# EEGAmp_SMT_MountHole_Castellated.net
KiCad netlist of a schematic drawn in EAGLE
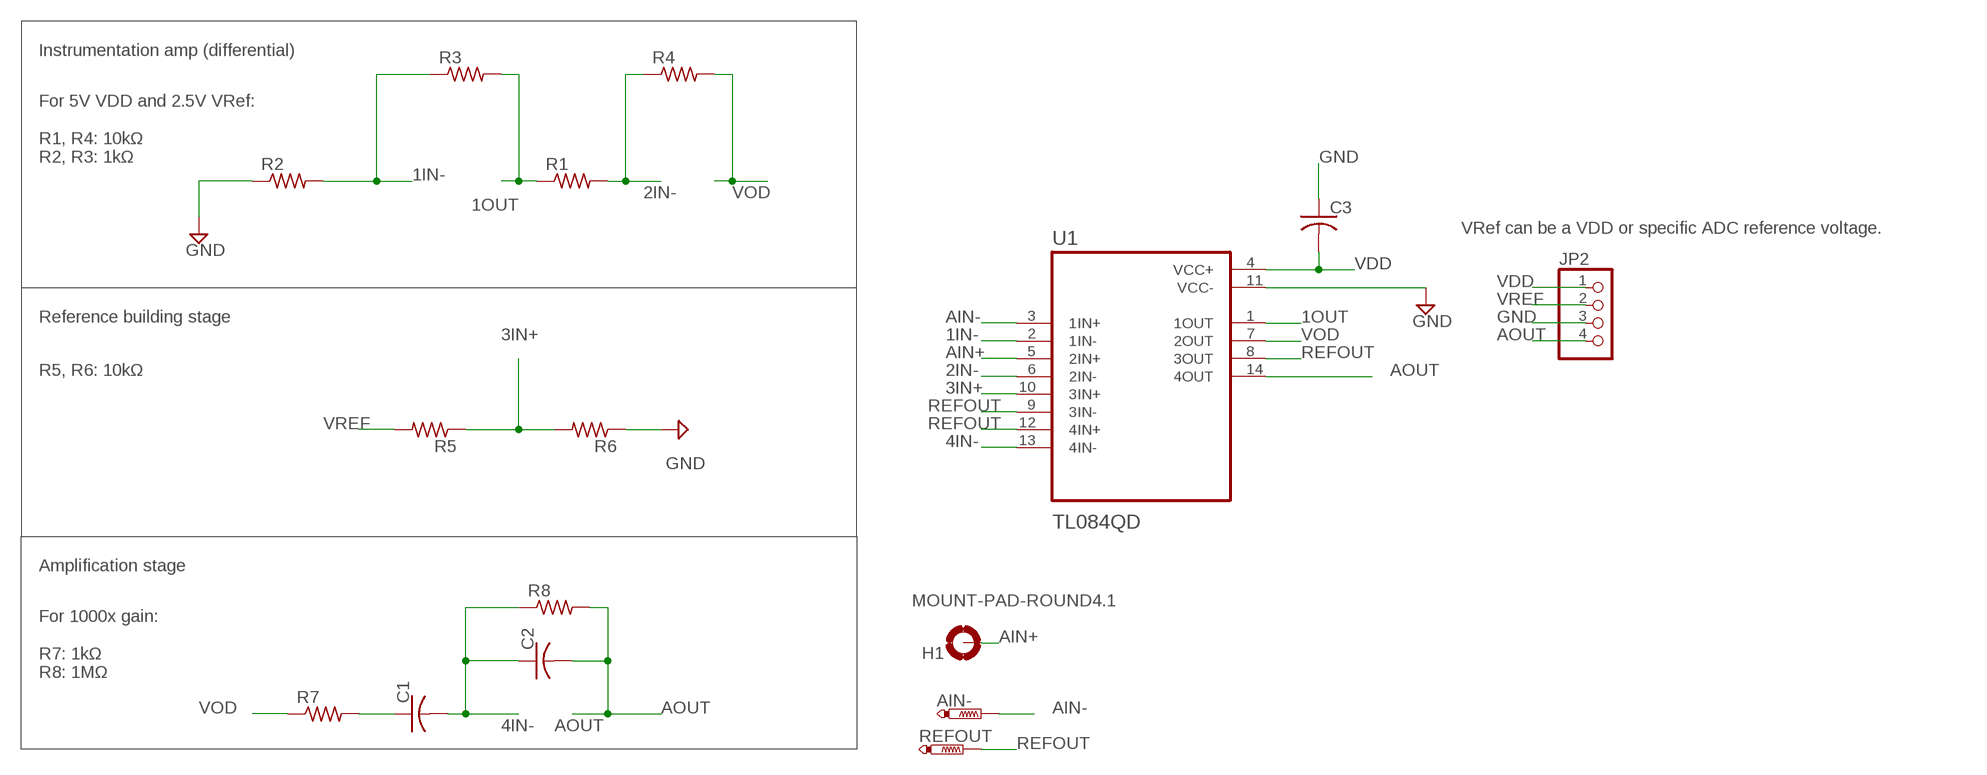
[diagram p0: schematic, sheet 1]

(export (version "E")
  (design (tool "Eeschema 10.0.6"))
  (components
    (comp (ref "AIN-")
      (value "PTR1PAD1-17")
      (footprint "eagle-import:P1-17")
      (libsource (lib "eagle-import") (part "PTR1PAD1-17"))
    )
    (comp (ref "C1")
      (value "C-USC0402")
      (footprint "eagle-import:C0402")
      (libsource (lib "eagle-import") (part "C-USC0402"))
    )
    (comp (ref "C2")
      (value "C-USC0402")
      (footprint "eagle-import:C0402")
      (libsource (lib "eagle-import") (part "C-USC0402"))
    )
    (comp (ref "C3")
      (value "C-USC0402")
      (footprint "eagle-import:C0402")
      (libsource (lib "eagle-import") (part "C-USC0402"))
    )
    (comp (ref "H1")
      (value "MOUNT-PAD-ROUND4.1")
      (footprint "eagle-import:4,1-PAD")
      (libsource (lib "eagle-import") (part "MOUNT-PAD-ROUND4.1"))
    )
    (comp (ref "JP2")
      (value "PINHD-1X4")
      (footprint "eagle-import:1X04")
      (libsource (lib "eagle-import") (part "PINHD-1X4"))
    )
    (comp (ref "R1")
      (value "R-US_R0402")
      (footprint "eagle-import:R0402")
      (libsource (lib "eagle-import") (part "R-US_R0402"))
    )
    (comp (ref "R2")
      (value "R-US_R0402")
      (footprint "eagle-import:R0402")
      (libsource (lib "eagle-import") (part "R-US_R0402"))
    )
    (comp (ref "R3")
      (value "R-US_R0402")
      (footprint "eagle-import:R0402")
      (libsource (lib "eagle-import") (part "R-US_R0402"))
    )
    (comp (ref "R4")
      (value "R-US_R0402")
      (footprint "eagle-import:R0402")
      (libsource (lib "eagle-import") (part "R-US_R0402"))
    )
    (comp (ref "R5")
      (value "R-US_R0402")
      (footprint "eagle-import:R0402")
      (libsource (lib "eagle-import") (part "R-US_R0402"))
    )
    (comp (ref "R6")
      (value "R-US_R0402")
      (footprint "eagle-import:R0402")
      (libsource (lib "eagle-import") (part "R-US_R0402"))
    )
    (comp (ref "R7")
      (value "R-US_R0402")
      (footprint "eagle-import:R0402")
      (libsource (lib "eagle-import") (part "R-US_R0402"))
    )
    (comp (ref "R8")
      (value "R-US_R0402")
      (footprint "eagle-import:R0402")
      (libsource (lib "eagle-import") (part "R-US_R0402"))
    )
    (comp (ref "REFOUT")
      (value "PTR1PAD1-17")
      (footprint "eagle-import:P1-17")
      (libsource (lib "eagle-import") (part "PTR1PAD1-17"))
    )
    (comp (ref "U1")
      (value "TL084QD")
      (footprint "eagle-import:SOIC127P600X175-14N")
      (fields (field (name "MF") "Texas Instruments"))
      (libsource (lib "eagle-import") (part "TL084QD"))
    )
  )
  (nets
    (net (code "1") (name "/1IN-") (class "Default")
      (node (ref "R2") (pin "2") (pinfunction "2_2") (pintype "passive"))
      (node (ref "R3") (pin "1") (pinfunction "1_1") (pintype "passive"))
      (node (ref "U1") (pin "2") (pinfunction "1IN-_2") (pintype "input"))
    )
    (net (code "2") (name "/1OUT") (class "Default")
      (node (ref "R1") (pin "1") (pinfunction "1_1") (pintype "passive"))
      (node (ref "R3") (pin "2") (pinfunction "2_2") (pintype "passive"))
      (node (ref "U1") (pin "1") (pinfunction "1OUT_1") (pintype "output"))
    )
    (net (code "3") (name "/2IN-") (class "Default")
      (node (ref "R1") (pin "2") (pinfunction "2_2") (pintype "passive"))
      (node (ref "R4") (pin "1") (pinfunction "1_1") (pintype "passive"))
      (node (ref "U1") (pin "6") (pinfunction "2IN-_6") (pintype "input"))
    )
    (net (code "4") (name "/3IN+") (class "Default")
      (node (ref "R5") (pin "1") (pinfunction "1_1") (pintype "passive"))
      (node (ref "R6") (pin "2") (pinfunction "2_2") (pintype "passive"))
      (node (ref "U1") (pin "10") (pinfunction "3IN+_10") (pintype "input"))
    )
    (net (code "5") (name "/4IN-") (class "Default")
      (node (ref "C1") (pin "2") (pinfunction "2_2") (pintype "passive"))
      (node (ref "C2") (pin "1") (pinfunction "1_1") (pintype "passive"))
      (node (ref "R8") (pin "1") (pinfunction "1_1") (pintype "passive"))
      (node (ref "U1") (pin "13") (pinfunction "4IN-_13") (pintype "input"))
    )
    (net (code "6") (name "/AIN+") (class "Default")
      (node (ref "H1") (pin "B4,1") (pinfunction "MOUNT_B4,1") (pintype "passive"))
      (node (ref "U1") (pin "5") (pinfunction "2IN+_5") (pintype "input"))
    )
    (net (code "7") (name "/AIN-") (class "Default")
      (node (ref "AIN-") (pin "TP") (pinfunction "TP_TP") (pintype "input"))
      (node (ref "U1") (pin "3") (pinfunction "1IN+_3") (pintype "input"))
    )
    (net (code "8") (name "/AOUT") (class "Default")
      (node (ref "C2") (pin "2") (pinfunction "2_2") (pintype "passive"))
      (node (ref "JP2") (pin "4") (pinfunction "4_4") (pintype "passive"))
      (node (ref "R8") (pin "2") (pinfunction "2_2") (pintype "passive"))
      (node (ref "U1") (pin "14") (pinfunction "4OUT_14") (pintype "output"))
    )
    (net (code "9") (name "/REFOUT") (class "Default")
      (node (ref "REFOUT") (pin "TP") (pinfunction "TP_TP") (pintype "input"))
      (node (ref "U1") (pin "12") (pinfunction "4IN+_12") (pintype "input"))
      (node (ref "U1") (pin "8") (pinfunction "3OUT_8") (pintype "output"))
      (node (ref "U1") (pin "9") (pinfunction "3IN-_9") (pintype "input"))
    )
    (net (code "10") (name "/VDD") (class "Default")
      (node (ref "C3") (pin "2") (pinfunction "2_2") (pintype "passive"))
      (node (ref "JP2") (pin "1") (pinfunction "1_1") (pintype "passive"))
      (node (ref "U1") (pin "4") (pinfunction "VCC+_4") (pintype "power_in"))
    )
    (net (code "11") (name "/VOD") (class "Default")
      (node (ref "R4") (pin "2") (pinfunction "2_2") (pintype "passive"))
      (node (ref "R7") (pin "1") (pinfunction "1_1") (pintype "passive"))
      (node (ref "U1") (pin "7") (pinfunction "2OUT_7") (pintype "output"))
    )
    (net (code "12") (name "/VREF") (class "Default")
      (node (ref "JP2") (pin "2") (pinfunction "2_2") (pintype "passive"))
      (node (ref "R5") (pin "2") (pinfunction "2_2") (pintype "passive"))
    )
    (net (code "13") (name "GND") (class "Default")
      (node (ref "C3") (pin "1") (pinfunction "1_1") (pintype "passive"))
      (node (ref "JP2") (pin "3") (pinfunction "3_3") (pintype "passive"))
      (node (ref "R2") (pin "1") (pinfunction "1_1") (pintype "passive"))
      (node (ref "R6") (pin "1") (pinfunction "1_1") (pintype "passive"))
      (node (ref "U1") (pin "11") (pinfunction "VCC-_11") (pintype "power_in"))
    )
    (net (code "14") (name "Net-(C1-Pad1)") (class "Default")
      (node (ref "C1") (pin "1") (pinfunction "1_1") (pintype "passive"))
      (node (ref "R7") (pin "2") (pinfunction "2_2") (pintype "passive"))
    )
  )
)
